# BMX055_Breakout.net
KiCad netlist of a schematic drawn in EAGLE
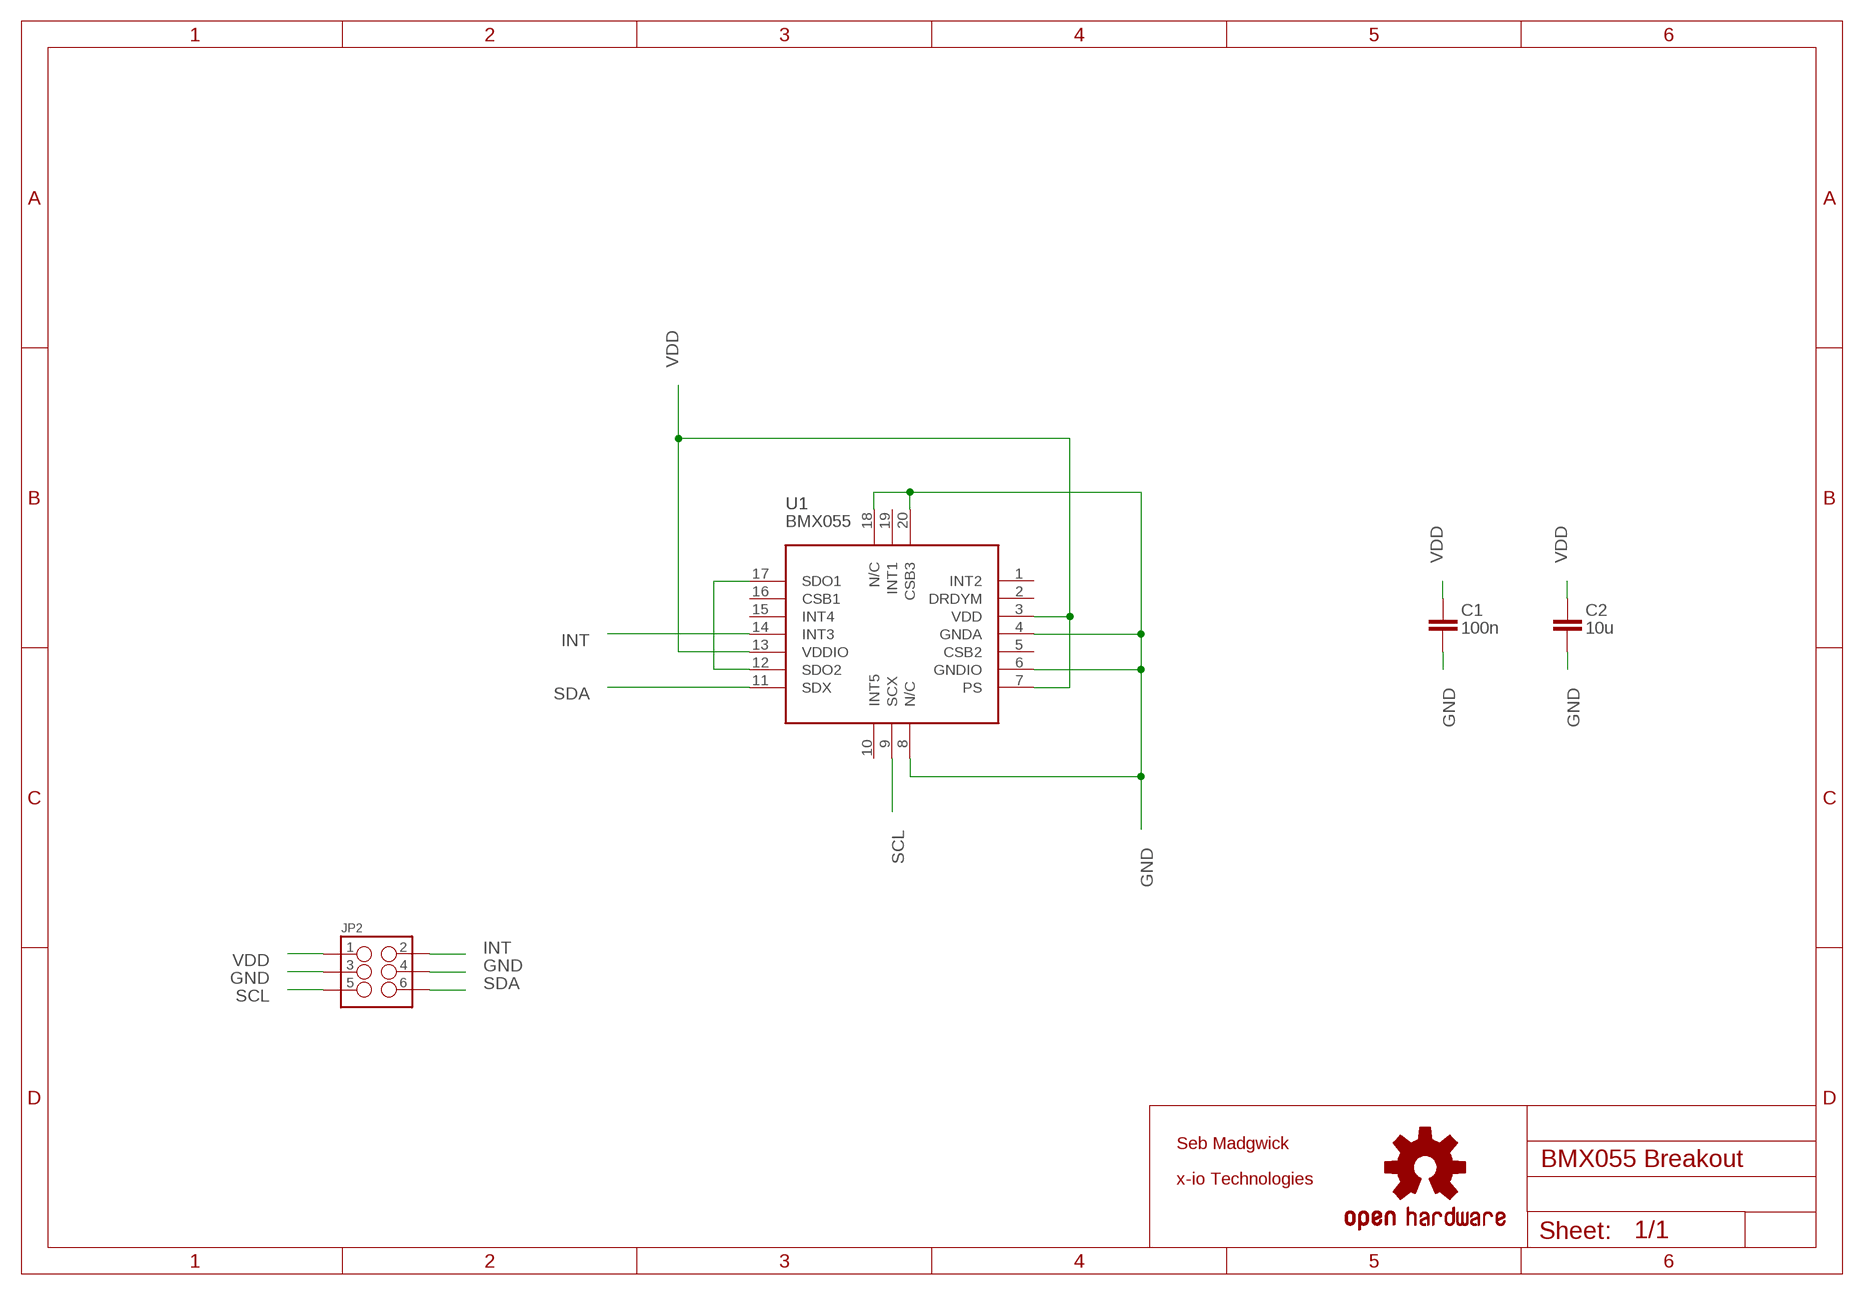
[diagram p0: schematic, sheet 1]

(export (version "E")
  (design (tool "Eeschema 10.0.6"))
  (components
    (comp (ref "C1")
      (value "100n")
      (footprint "eagle-import:0603-CAP")
      (libsource (lib "eagle-import") (part "CAP0603-CAP"))
    )
    (comp (ref "C2")
      (value "10u")
      (footprint "eagle-import:0603-CAP")
      (libsource (lib "eagle-import") (part "CAP0603-CAP"))
    )
    (comp (ref "JP2")
      (value "M03X2POGO_PINS")
      (footprint "eagle-import:2X3_POGO")
      (libsource (lib "eagle-import") (part "M03X2POGO_PINS"))
    )
    (comp (ref "LOGO1")
      (value "OSHW-LOGOS")
      (footprint "eagle-import:OSHW-LOGO-S")
      (libsource (lib "eagle-import") (part "OSHW-LOGOS"))
    )
    (comp (ref "U1")
      (value "BMX055")
      (footprint "eagle-import:BMX055")
      (libsource (lib "eagle-import") (part "BMX055"))
    )
  )
  (nets
    (net (code "1") (name "/GND") (class "Default")
      (node (ref "C1") (pin "2") (pinfunction "2_2") (pintype "passive"))
      (node (ref "C2") (pin "2") (pinfunction "2_2") (pintype "passive"))
      (node (ref "JP2") (pin "P$3") (pinfunction "3_P$3") (pintype "bidirectional"))
      (node (ref "JP2") (pin "P$4") (pinfunction "4_P$4") (pintype "bidirectional"))
      (node (ref "U1") (pin "18") (pinfunction "N/C_18") (pintype "bidirectional"))
      (node (ref "U1") (pin "20") (pinfunction "CSB3_20") (pintype "bidirectional"))
      (node (ref "U1") (pin "4") (pinfunction "GNDA_4") (pintype "bidirectional"))
      (node (ref "U1") (pin "6") (pinfunction "GNDIO_6") (pintype "bidirectional"))
      (node (ref "U1") (pin "8") (pinfunction "N/C_8") (pintype "bidirectional"))
    )
    (net (code "2") (name "/INT") (class "Default")
      (node (ref "JP2") (pin "P$2") (pinfunction "2_P$2") (pintype "bidirectional"))
      (node (ref "U1") (pin "14") (pinfunction "INT3_14") (pintype "bidirectional"))
    )
    (net (code "3") (name "/SCL") (class "Default")
      (node (ref "JP2") (pin "P$5") (pinfunction "5_P$5") (pintype "bidirectional"))
      (node (ref "U1") (pin "9") (pinfunction "SCX_9") (pintype "bidirectional"))
    )
    (net (code "4") (name "/SDA") (class "Default")
      (node (ref "JP2") (pin "P$6") (pinfunction "6_P$6") (pintype "bidirectional"))
      (node (ref "U1") (pin "11") (pinfunction "SDX_11") (pintype "bidirectional"))
    )
    (net (code "5") (name "/VDD") (class "Default")
      (node (ref "C1") (pin "1") (pinfunction "1_1") (pintype "passive"))
      (node (ref "C2") (pin "1") (pinfunction "1_1") (pintype "passive"))
      (node (ref "JP2") (pin "P$1") (pinfunction "1_P$1") (pintype "bidirectional"))
      (node (ref "U1") (pin "13") (pinfunction "VDDIO_13") (pintype "bidirectional"))
      (node (ref "U1") (pin "3") (pinfunction "VDD_3") (pintype "bidirectional"))
      (node (ref "U1") (pin "7") (pinfunction "PS_7") (pintype "bidirectional"))
    )
    (net (code "6") (name "Net-(U1-SDO1)") (class "Default")
      (node (ref "U1") (pin "12") (pinfunction "SDO2_12") (pintype "bidirectional"))
      (node (ref "U1") (pin "17") (pinfunction "SDO1_17") (pintype "bidirectional"))
    )
    (net (code "7") (name "unconnected-(U1-CSB1-Pad16)") (class "Default")
      (node (ref "U1") (pin "16") (pinfunction "CSB1_16") (pintype "bidirectional"))
    )
    (net (code "8") (name "unconnected-(U1-CSB2-Pad5)") (class "Default")
      (node (ref "U1") (pin "5") (pinfunction "CSB2_5") (pintype "bidirectional"))
    )
    (net (code "9") (name "unconnected-(U1-DRDYM-Pad2)") (class "Default")
      (node (ref "U1") (pin "2") (pinfunction "DRDYM_2") (pintype "bidirectional"))
    )
    (net (code "10") (name "unconnected-(U1-INT1-Pad19)") (class "Default")
      (node (ref "U1") (pin "19") (pinfunction "INT1_19") (pintype "bidirectional"))
    )
    (net (code "11") (name "unconnected-(U1-INT2-Pad1)") (class "Default")
      (node (ref "U1") (pin "1") (pinfunction "INT2_1") (pintype "bidirectional"))
    )
    (net (code "12") (name "unconnected-(U1-INT4-Pad15)") (class "Default")
      (node (ref "U1") (pin "15") (pinfunction "INT4_15") (pintype "bidirectional"))
    )
    (net (code "13") (name "unconnected-(U1-INT5-Pad10)") (class "Default")
      (node (ref "U1") (pin "10") (pinfunction "INT5_10") (pintype "bidirectional"))
    )
  )
)
